# Wii.net
KiCad netlist of a schematic drawn in EAGLE
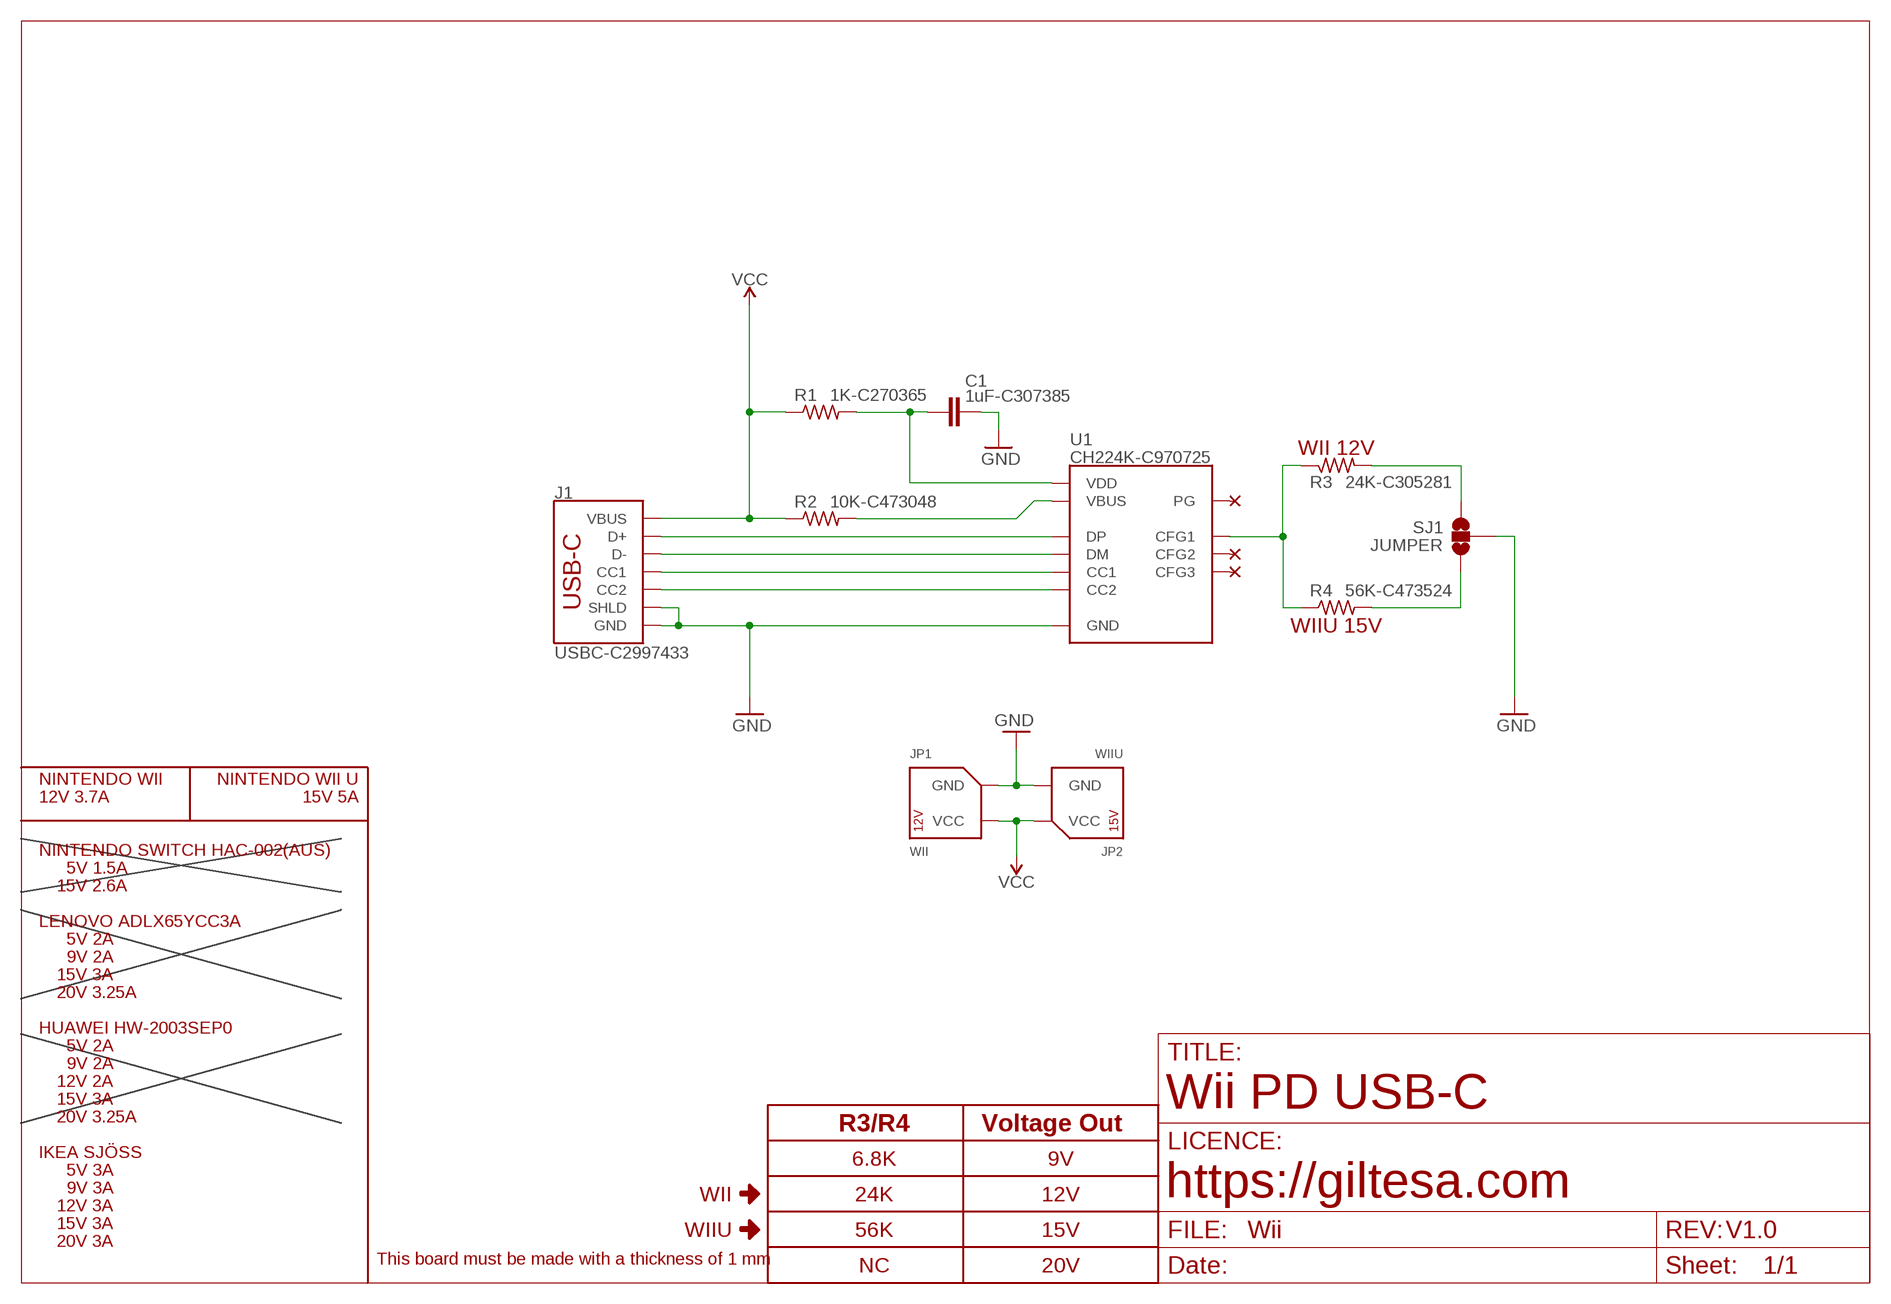
[diagram p0: schematic, sheet 1]

(export (version "E")
  (design (tool "Eeschema 10.0.6"))
  (components
    (comp (ref "C1")
      (value "1uF-C307385")
      (footprint "eagle-import:C0201")
      (libsource (lib "eagle-import") (part "C0201"))
    )
    (comp (ref "J1")
      (value "USBC-C2997433")
      (footprint "eagle-import:USB-C_16P")
      (libsource (lib "eagle-import") (part "USB-C_16P_DATA"))
    )
    (comp (ref "JP1")
      (value "WII")
      (footprint "eagle-import:WII_1X02")
      (libsource (lib "eagle-import") (part "WII_PWD_CONNECTOR"))
    )
    (comp (ref "JP2")
      (value "WIIU")
      (footprint "eagle-import:WIIU_1X02")
      (libsource (lib "eagle-import") (part "WII_U_PWD_CONNECTOR"))
    )
    (comp (ref "R1")
      (value "1K-C270365")
      (footprint "eagle-import:R0201")
      (libsource (lib "eagle-import") (part "R0201"))
    )
    (comp (ref "R2")
      (value "10K-C473048")
      (footprint "eagle-import:R0201")
      (libsource (lib "eagle-import") (part "R0201"))
    )
    (comp (ref "R3")
      (value "24K-C305281")
      (footprint "eagle-import:R0201")
      (libsource (lib "eagle-import") (part "R0201"))
    )
    (comp (ref "R4")
      (value "56K-C473524")
      (footprint "eagle-import:R0201")
      (libsource (lib "eagle-import") (part "R0201"))
    )
    (comp (ref "SJ1")
      (value "JUMPER")
      (footprint "eagle-import:JUMPER-SMD-3_NO_SILK")
      (libsource (lib "eagle-import") (part "JUMPER-SMD-3_NO"))
    )
    (comp (ref "U1")
      (value "CH224K-C970725")
      (footprint "eagle-import:ESSOP10")
      (libsource (lib "eagle-import") (part "CH224K"))
    )
  )
  (nets
    (net (code "1") (name "GND") (class "Default")
      (node (ref "C1") (pin "2") (pinfunction "2_2") (pintype "passive"))
      (node (ref "J1") (pin "GND1") (pinfunction "GND_GND1") (pintype "bidirectional"))
      (node (ref "J1") (pin "GND2") (pinfunction "GND_GND2") (pintype "bidirectional"))
      (node (ref "J1") (pin "SHLD1") (pinfunction "SHLD_SHLD1") (pintype "bidirectional"))
      (node (ref "J1") (pin "SHLD2") (pinfunction "SHLD_SHLD2") (pintype "bidirectional"))
      (node (ref "J1") (pin "SHLD3") (pinfunction "SHLD_SHLD3") (pintype "bidirectional"))
      (node (ref "J1") (pin "SHLD4") (pinfunction "SHLD_SHLD4") (pintype "bidirectional"))
      (node (ref "JP1") (pin "GND1") (pinfunction "GND_GND1") (pintype "output"))
      (node (ref "JP2") (pin "GND1") (pinfunction "GND_GND1") (pintype "output"))
      (node (ref "SJ1") (pin "2") (pinfunction "2_2") (pintype "passive"))
      (node (ref "U1") (pin "0") (pinfunction "GND_0") (pintype "bidirectional"))
    )
    (net (code "2") (name "Net-(J1-CC1)") (class "Default")
      (node (ref "J1") (pin "A5-CC1") (pinfunction "CC1_A5-CC1") (pintype "bidirectional"))
      (node (ref "U1") (pin "7") (pinfunction "CC1_7") (pintype "bidirectional"))
    )
    (net (code "3") (name "Net-(J1-CC2)") (class "Default")
      (node (ref "J1") (pin "B5-CC2") (pinfunction "CC2_B5-CC2") (pintype "bidirectional"))
      (node (ref "U1") (pin "6") (pinfunction "CC2_6") (pintype "bidirectional"))
    )
    (net (code "4") (name "Net-(R3-Pad2)") (class "Default")
      (node (ref "R3") (pin "2") (pinfunction "2_2") (pintype "passive"))
      (node (ref "SJ1") (pin "1") (pinfunction "1_1") (pintype "passive"))
    )
    (net (code "5") (name "Net-(R4-Pad2)") (class "Default")
      (node (ref "R4") (pin "2") (pinfunction "2_2") (pintype "passive"))
      (node (ref "SJ1") (pin "3") (pinfunction "3_3") (pintype "passive"))
    )
    (net (code "6") (name "Net-(U1-CFG1)") (class "Default")
      (node (ref "R3") (pin "1") (pinfunction "1_1") (pintype "passive"))
      (node (ref "R4") (pin "1") (pinfunction "1_1") (pintype "passive"))
      (node (ref "U1") (pin "9") (pinfunction "CFG1_9") (pintype "bidirectional"))
    )
    (net (code "7") (name "Net-(U1-DM)") (class "Default")
      (node (ref "J1") (pin "A7-DN1") (pinfunction "D-_A7-DN1") (pintype "bidirectional"))
      (node (ref "J1") (pin "B7-DN2") (pinfunction "D-_B7-DN2") (pintype "bidirectional"))
      (node (ref "U1") (pin "5") (pinfunction "DM_5") (pintype "bidirectional"))
    )
    (net (code "8") (name "Net-(U1-DP)") (class "Default")
      (node (ref "J1") (pin "A6-DP1") (pinfunction "D+_A6-DP1") (pintype "bidirectional"))
      (node (ref "J1") (pin "B6-DP2") (pinfunction "D+_B6-DP2") (pintype "bidirectional"))
      (node (ref "U1") (pin "4") (pinfunction "DP_4") (pintype "bidirectional"))
    )
    (net (code "9") (name "Net-(U1-VBUS)") (class "Default")
      (node (ref "R2") (pin "2") (pinfunction "2_2") (pintype "passive"))
      (node (ref "U1") (pin "8") (pinfunction "VBUS_8") (pintype "bidirectional"))
    )
    (net (code "10") (name "Net-(U1-VDD)") (class "Default")
      (node (ref "C1") (pin "1") (pinfunction "1_1") (pintype "passive"))
      (node (ref "R1") (pin "2") (pinfunction "2_2") (pintype "passive"))
      (node (ref "U1") (pin "1") (pinfunction "VDD_1") (pintype "bidirectional"))
    )
    (net (code "11") (name "VCC") (class "Default")
      (node (ref "J1") (pin "VBUS1") (pinfunction "VBUS_VBUS1") (pintype "bidirectional"))
      (node (ref "J1") (pin "VBUS2") (pinfunction "VBUS_VBUS2") (pintype "bidirectional"))
      (node (ref "JP1") (pin "VCC1") (pinfunction "VCC_VCC1") (pintype "power_in"))
      (node (ref "JP2") (pin "VCC1") (pinfunction "VCC_VCC1") (pintype "power_in"))
      (node (ref "R1") (pin "1") (pinfunction "1_1") (pintype "passive"))
      (node (ref "R2") (pin "1") (pinfunction "1_1") (pintype "passive"))
    )
    (net (code "12") (name "unconnected-(U1-CFG2-Pad2)") (class "Default")
      (node (ref "U1") (pin "2") (pinfunction "CFG2_2") (pintype "bidirectional"))
    )
    (net (code "13") (name "unconnected-(U1-CFG3-Pad3)") (class "Default")
      (node (ref "U1") (pin "3") (pinfunction "CFG3_3") (pintype "bidirectional"))
    )
    (net (code "14") (name "unconnected-(U1-PG-Pad10)") (class "Default")
      (node (ref "U1") (pin "10") (pinfunction "PG_10") (pintype "bidirectional"))
    )
  )
)
